# Sensorboard.net
KiCad netlist of a schematic drawn in EAGLE
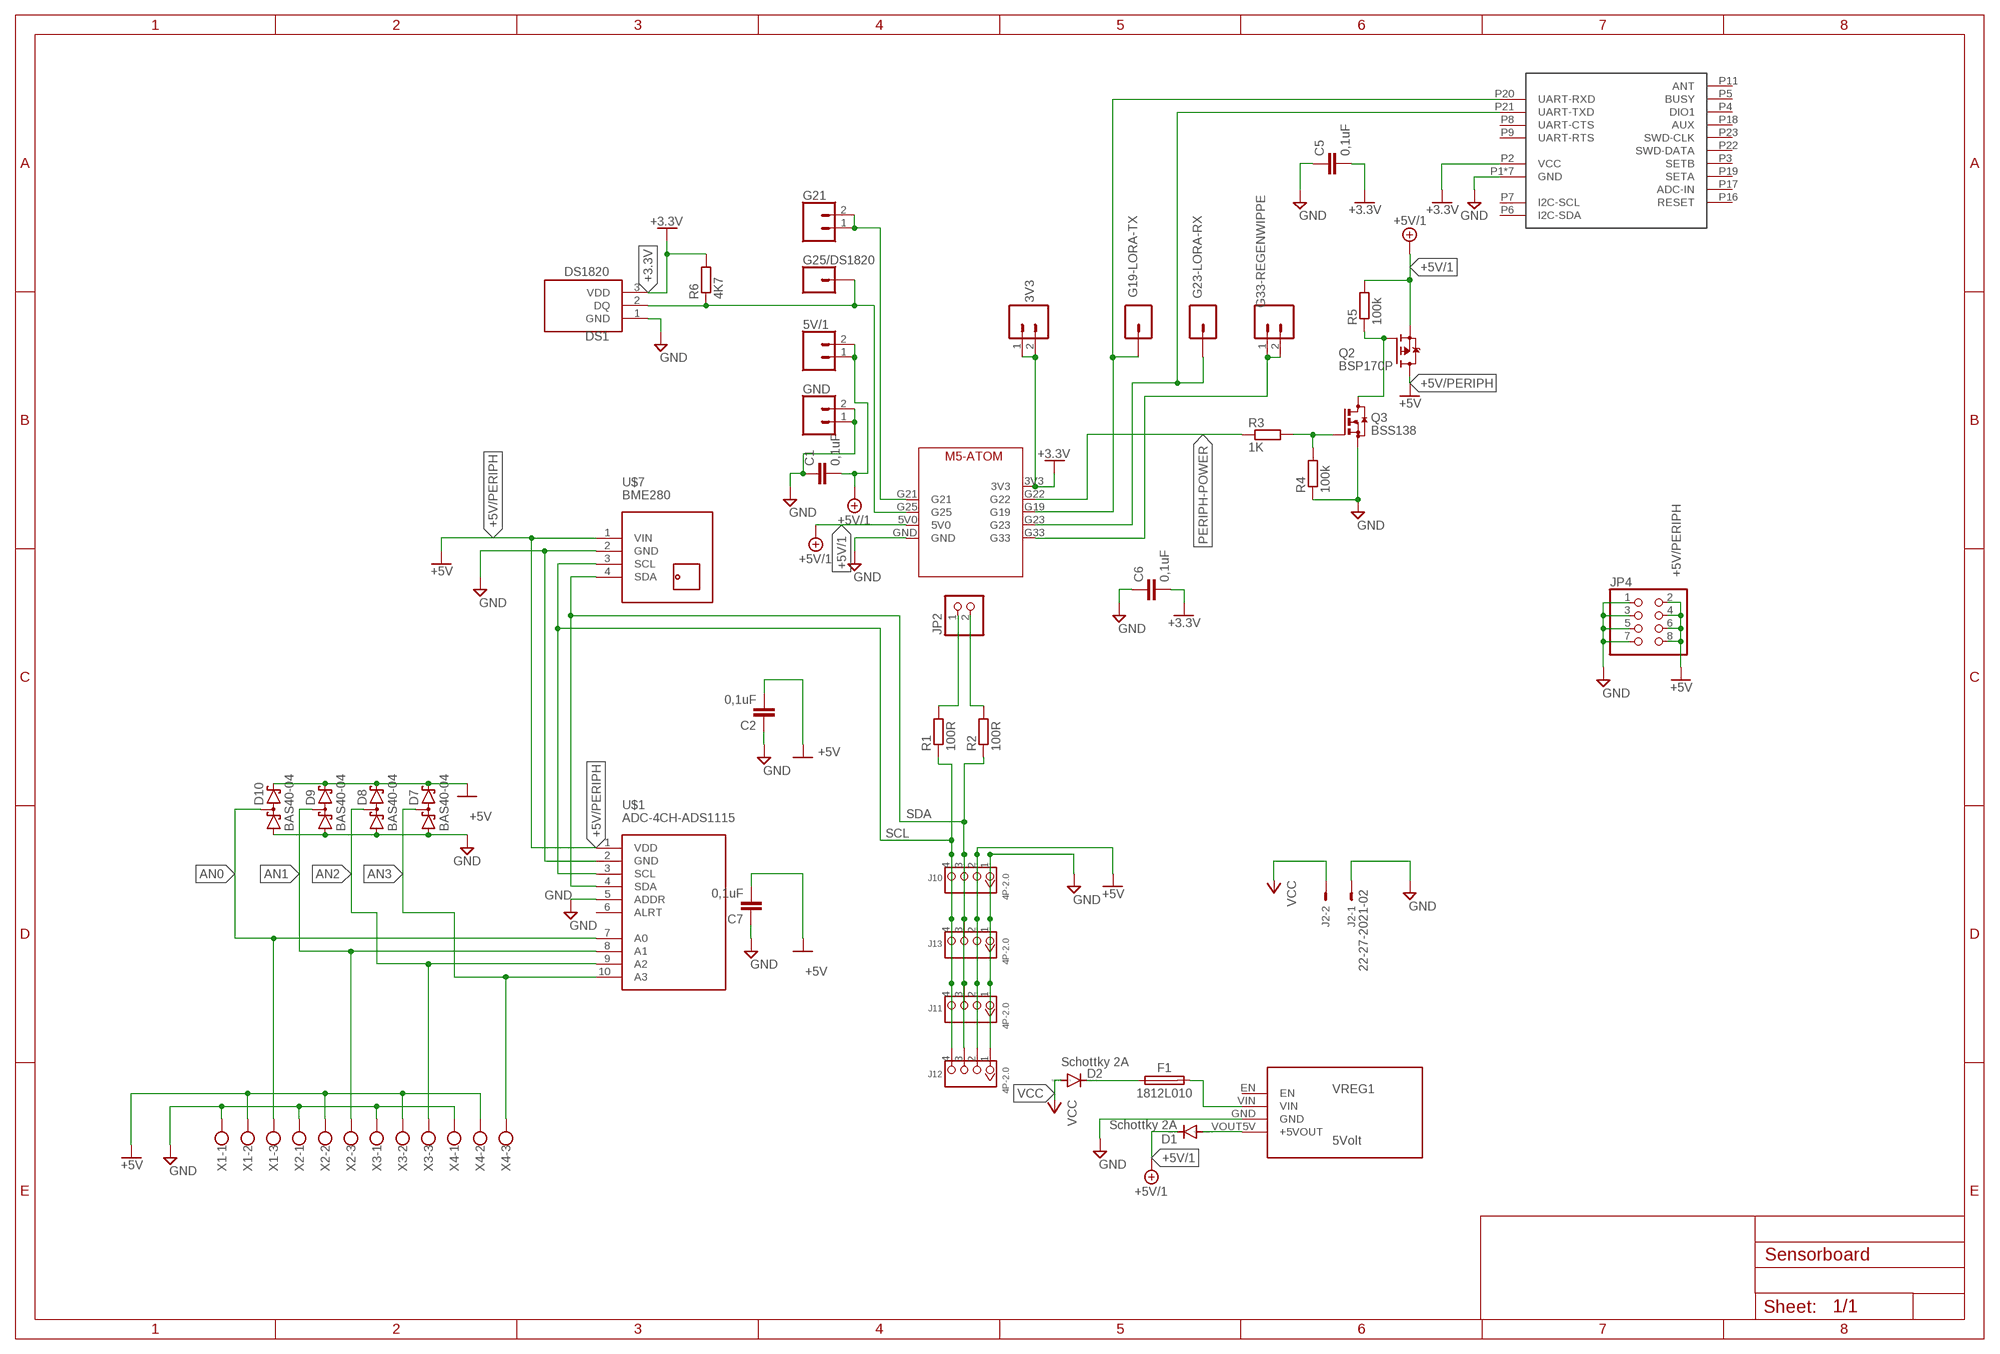
[diagram p0: schematic, sheet 1]

(export (version "E")
  (design (tool "Eeschema 10.0.6"))
  (components
    (comp (ref "3V3")
      (value "CONN_02")
      (footprint "eagle-import:1X02")
      (libsource (lib "eagle-import") (part "CONN_02"))
    )
    (comp (ref "5V/1")
      (value "CONN_02")
      (footprint "eagle-import:1X02")
      (libsource (lib "eagle-import") (part "CONN_02"))
    )
    (comp (ref "C1")
      (value "0,1uF")
      (footprint "eagle-import:C025-025X050")
      (libsource (lib "eagle-import") (part "C-EU025-025X050"))
    )
    (comp (ref "C2")
      (value "0,1uF")
      (footprint "eagle-import:C025-025X050")
      (libsource (lib "eagle-import") (part "C-EU025-025X050"))
    )
    (comp (ref "C5")
      (value "0,1uF")
      (footprint "eagle-import:C025-025X050")
      (libsource (lib "eagle-import") (part "C-EU025-025X050"))
    )
    (comp (ref "C6")
      (value "0,1uF")
      (footprint "eagle-import:C025-025X050")
      (libsource (lib "eagle-import") (part "C-EU025-025X050"))
    )
    (comp (ref "C7")
      (value "0,1uF")
      (footprint "eagle-import:C025-025X050")
      (libsource (lib "eagle-import") (part "C-EU025-025X050"))
    )
    (comp (ref "D1")
      (value "Schottky 2A")
      (footprint "eagle-import:DO41-10")
      (libsource (lib "eagle-import") (part "1N4004"))
    )
    (comp (ref "D2")
      (value "Schottky 2A")
      (footprint "eagle-import:DO41-10")
      (libsource (lib "eagle-import") (part "1N4004"))
    )
    (comp (ref "D7")
      (value "BAS40-04")
      (footprint "eagle-import:SOT23")
      (libsource (lib "eagle-import") (part "BAS40-04"))
    )
    (comp (ref "D8")
      (value "BAS40-04")
      (footprint "eagle-import:SOT23")
      (libsource (lib "eagle-import") (part "BAS40-04"))
    )
    (comp (ref "D9")
      (value "BAS40-04")
      (footprint "eagle-import:SOT23")
      (libsource (lib "eagle-import") (part "BAS40-04"))
    )
    (comp (ref "D10")
      (value "BAS40-04")
      (footprint "eagle-import:SOT23")
      (libsource (lib "eagle-import") (part "BAS40-04"))
    )
    (comp (ref "DS1")
      (value "DS1820")
      (footprint "eagle-import:DS1820-TO92")
      (libsource (lib "eagle-import") (part "DS1820"))
    )
    (comp (ref "F1")
      (value "1812L010")
      (footprint "eagle-import:FUSC4532X125")
      (fields (field (name "MANUFACTURER") "Littlefuse"))
      (libsource (lib "eagle-import") (part "1812L010"))
    )
    (comp (ref "G19-LORA-TX")
      (value "CONN_01")
      (footprint "eagle-import:1X01")
      (libsource (lib "eagle-import") (part "CONN_01"))
    )
    (comp (ref "G21")
      (value "CONN_02")
      (footprint "eagle-import:1X02")
      (libsource (lib "eagle-import") (part "CONN_02"))
    )
    (comp (ref "G23-LORA-RX")
      (value "CONN_01")
      (footprint "eagle-import:1X01")
      (libsource (lib "eagle-import") (part "CONN_01"))
    )
    (comp (ref "G25/DS1820")
      (value "CONN_01")
      (footprint "eagle-import:1X01")
      (libsource (lib "eagle-import") (part "CONN_01"))
    )
    (comp (ref "G33-REGENWIPPE")
      (value "CONN_02")
      (footprint "eagle-import:1X02")
      (libsource (lib "eagle-import") (part "CONN_02"))
    )
    (comp (ref "GND")
      (value "CONN_02")
      (footprint "eagle-import:1X02")
      (libsource (lib "eagle-import") (part "CONN_02"))
    )
    (comp (ref "J2")
      (value "22-27-2021-02")
      (footprint "eagle-import:6410-02")
      (fields (field (name "MF") "MOLEX"))
      (libsource (lib "eagle-import") (part "22-?-0227-2021"))
    )
    (comp (ref "J10")
      (value "4P-2.0")
      (footprint "eagle-import:HW4-2.0")
      (libsource (lib "eagle-import") (part "GROVE-CONNECTOR-DIP(4P-2.0)"))
    )
    (comp (ref "J11")
      (value "4P-2.0")
      (footprint "eagle-import:HW4-2.0")
      (libsource (lib "eagle-import") (part "GROVE-CONNECTOR-DIP(4P-2.0)"))
    )
    (comp (ref "J12")
      (value "4P-2.0")
      (footprint "eagle-import:HW4-2.0")
      (libsource (lib "eagle-import") (part "GROVE-CONNECTOR-DIP(4P-2.0)"))
    )
    (comp (ref "J13")
      (value "4P-2.0")
      (footprint "eagle-import:HW4-2.0")
      (libsource (lib "eagle-import") (part "GROVE-CONNECTOR-DIP(4P-2.0)"))
    )
    (comp (ref "JP2")
      (value "PINHD-1X2")
      (footprint "eagle-import:1X02")
      (libsource (lib "eagle-import") (part "PINHD-1X2"))
    )
    (comp (ref "JP4")
      (value "PINHD-2X4")
      (footprint "eagle-import:2X04")
      (libsource (lib "eagle-import") (part "PINHD-2X4"))
    )
    (comp (ref "M5-ATOM")
      (value "M5-ATOM")
      (footprint "eagle-import:M5-ATOM")
      (libsource (lib "eagle-import") (part "M5-ATOM"))
    )
    (comp (ref "Q2")
      (value "BSP170P")
      (footprint "eagle-import:SOT223")
      (libsource (lib "eagle-import") (part "BSP170P"))
    )
    (comp (ref "Q3")
      (value "BSS138")
      (footprint "eagle-import:SOT23")
      (libsource (lib "eagle-import") (part "BSS123"))
    )
    (comp (ref "R1")
      (value "100R")
      (footprint "eagle-import:0204_7")
      (libsource (lib "eagle-import") (part "R-EU_0204/7"))
    )
    (comp (ref "R2")
      (value "100R")
      (footprint "eagle-import:0204_7")
      (libsource (lib "eagle-import") (part "R-EU_0204/7"))
    )
    (comp (ref "R3")
      (value "1K")
      (footprint "eagle-import:R1206")
      (libsource (lib "eagle-import") (part "R-EU_R1206"))
    )
    (comp (ref "R4")
      (value "100k")
      (footprint "eagle-import:R1206")
      (libsource (lib "eagle-import") (part "R-EU_R1206"))
    )
    (comp (ref "R5")
      (value "100k")
      (footprint "eagle-import:R1206")
      (libsource (lib "eagle-import") (part "R-EU_R1206"))
    )
    (comp (ref "R6")
      (value "4K7")
      (footprint "eagle-import:R1206")
      (libsource (lib "eagle-import") (part "R-EU_R1206"))
    )
    (comp (ref "U$1")
      (value "ADC-4CH-ADS1115")
      (footprint "eagle-import:ADC-4CH-ADS1115")
      (libsource (lib "eagle-import") (part "ADC-4CH-ADS1115"))
    )
    (comp (ref "U$2")
      (value "E78-868LN22S")
      (footprint "eagle-import:E78-868LN22S")
      (libsource (lib "eagle-import") (part "E78-868LN22S"))
    )
    (comp (ref "U$7")
      (value "BME280")
      (footprint "eagle-import:TEMP-HUM-PRES-BME280")
      (libsource (lib "eagle-import") (part "TEMP-HUM-PRES-BME280"))
    )
    (comp (ref "VREG1")
      (value "5Volt")
      (footprint "eagle-import:VREG-STEPDOWN")
      (libsource (lib "eagle-import") (part "VREG-STEPDOWN"))
    )
    (comp (ref "X1")
      (value "W237-103-RB")
      (footprint "eagle-import:W237-103-RB")
      (libsource (lib "eagle-import") (part "W237-103-RB"))
    )
    (comp (ref "X2")
      (value "W237-103-RB")
      (footprint "eagle-import:W237-103-RB")
      (libsource (lib "eagle-import") (part "W237-103-RB"))
    )
    (comp (ref "X3")
      (value "W237-103-RB")
      (footprint "eagle-import:W237-103-RB")
      (libsource (lib "eagle-import") (part "W237-103-RB"))
    )
    (comp (ref "X4")
      (value "W237-103-RB")
      (footprint "eagle-import:W237-103-RB")
      (libsource (lib "eagle-import") (part "W237-103-RB"))
    )
  )
  (nets
    (net (code "1") (name "+3.3V") (class "Default")
      (node (ref "3V3") (pin "1") (pinfunction "1_1") (pintype "passive"))
      (node (ref "3V3") (pin "2") (pinfunction "2_2") (pintype "passive"))
      (node (ref "C5") (pin "2") (pinfunction "2_2") (pintype "passive"))
      (node (ref "C6") (pin "2") (pinfunction "2_2") (pintype "passive"))
      (node (ref "DS1") (pin "3") (pinfunction "VDD_3") (pintype "bidirectional"))
      (node (ref "M5-ATOM") (pin "3V3") (pinfunction "3V3_3V3") (pintype "bidirectional"))
      (node (ref "R6") (pin "2") (pinfunction "2_2") (pintype "passive"))
      (node (ref "U$2") (pin "P2") (pinfunction "VCC_P2") (pintype "bidirectional"))
    )
    (net (code "2") (name "+5V{slash}1") (class "Default")
      (node (ref "5V/1") (pin "1") (pinfunction "1_1") (pintype "passive"))
      (node (ref "5V/1") (pin "2") (pinfunction "2_2") (pintype "passive"))
      (node (ref "C1") (pin "2") (pinfunction "2_2") (pintype "passive"))
      (node (ref "D1") (pin "C") (pinfunction "C_C") (pintype "passive"))
      (node (ref "M5-ATOM") (pin "5V0") (pinfunction "5V0_5V0") (pintype "bidirectional"))
      (node (ref "Q2") (pin "3") (pinfunction "S_3") (pintype "passive"))
      (node (ref "R5") (pin "2") (pinfunction "2_2") (pintype "passive"))
    )
    (net (code "3") (name "+5V{slash}PERIPH") (class "Default")
      (node (ref "C2") (pin "2") (pinfunction "2_2") (pintype "passive"))
      (node (ref "C7") (pin "2") (pinfunction "2_2") (pintype "passive"))
      (node (ref "D10") (pin "2") (pinfunction "C2_2") (pintype "passive"))
      (node (ref "D7") (pin "2") (pinfunction "C2_2") (pintype "passive"))
      (node (ref "D8") (pin "2") (pinfunction "C2_2") (pintype "passive"))
      (node (ref "D9") (pin "2") (pinfunction "C2_2") (pintype "passive"))
      (node (ref "J10") (pin "2") (pinfunction "2_2") (pintype "bidirectional"))
      (node (ref "J11") (pin "2") (pinfunction "2_2") (pintype "bidirectional"))
      (node (ref "J12") (pin "2") (pinfunction "2_2") (pintype "bidirectional"))
      (node (ref "J13") (pin "2") (pinfunction "2_2") (pintype "bidirectional"))
      (node (ref "JP4") (pin "2") (pinfunction "2_2") (pintype "passive"))
      (node (ref "JP4") (pin "4") (pinfunction "4_4") (pintype "passive"))
      (node (ref "JP4") (pin "6") (pinfunction "6_6") (pintype "passive"))
      (node (ref "JP4") (pin "8") (pinfunction "8_8") (pintype "passive"))
      (node (ref "Q2") (pin "2") (pinfunction "D_2") (pintype "passive"))
      (node (ref "Q2") (pin "4") (pinfunction "D_4") (pintype "passive"))
      (node (ref "U$1") (pin "1") (pinfunction "VDD_1") (pintype "power_in"))
      (node (ref "U$7") (pin "1") (pinfunction "VIN_1") (pintype "power_in"))
      (node (ref "X1") (pin "2") (pinfunction "KL_2") (pintype "passive"))
      (node (ref "X2") (pin "2") (pinfunction "KL_2") (pintype "passive"))
      (node (ref "X3") (pin "2") (pinfunction "KL_2") (pintype "passive"))
      (node (ref "X4") (pin "2") (pinfunction "KL_2") (pintype "passive"))
    )
    (net (code "4") (name "/SCL") (class "Default")
      (node (ref "J10") (pin "4") (pinfunction "4_4") (pintype "bidirectional"))
      (node (ref "J11") (pin "4") (pinfunction "4_4") (pintype "bidirectional"))
      (node (ref "J12") (pin "4") (pinfunction "4_4") (pintype "bidirectional"))
      (node (ref "J13") (pin "4") (pinfunction "4_4") (pintype "bidirectional"))
      (node (ref "R1") (pin "1") (pinfunction "1_1") (pintype "passive"))
      (node (ref "U$1") (pin "3") (pinfunction "SCL_3") (pintype "bidirectional"))
      (node (ref "U$7") (pin "3") (pinfunction "SCL_3") (pintype "bidirectional"))
    )
    (net (code "5") (name "/SDA") (class "Default")
      (node (ref "J10") (pin "3") (pinfunction "3_3") (pintype "bidirectional"))
      (node (ref "J11") (pin "3") (pinfunction "3_3") (pintype "bidirectional"))
      (node (ref "J12") (pin "3") (pinfunction "3_3") (pintype "bidirectional"))
      (node (ref "J13") (pin "3") (pinfunction "3_3") (pintype "bidirectional"))
      (node (ref "R2") (pin "1") (pinfunction "1_1") (pintype "passive"))
      (node (ref "U$1") (pin "4") (pinfunction "SDA_4") (pintype "bidirectional"))
      (node (ref "U$7") (pin "4") (pinfunction "SDA_4") (pintype "bidirectional"))
    )
    (net (code "6") (name "AN0") (class "Default")
      (node (ref "D10") (pin "3") (pinfunction "C1A2_3") (pintype "passive"))
      (node (ref "U$1") (pin "7") (pinfunction "A0_7") (pintype "input"))
      (node (ref "X1") (pin "3") (pinfunction "KL_3") (pintype "passive"))
    )
    (net (code "7") (name "AN1") (class "Default")
      (node (ref "D9") (pin "3") (pinfunction "C1A2_3") (pintype "passive"))
      (node (ref "U$1") (pin "8") (pinfunction "A1_8") (pintype "input"))
      (node (ref "X2") (pin "3") (pinfunction "KL_3") (pintype "passive"))
    )
    (net (code "8") (name "AN2") (class "Default")
      (node (ref "D8") (pin "3") (pinfunction "C1A2_3") (pintype "passive"))
      (node (ref "U$1") (pin "9") (pinfunction "A2_9") (pintype "input"))
      (node (ref "X3") (pin "3") (pinfunction "KL_3") (pintype "passive"))
    )
    (net (code "9") (name "AN3") (class "Default")
      (node (ref "D7") (pin "3") (pinfunction "C1A2_3") (pintype "passive"))
      (node (ref "U$1") (pin "10") (pinfunction "A3_10") (pintype "input"))
      (node (ref "X4") (pin "3") (pinfunction "KL_3") (pintype "passive"))
    )
    (net (code "10") (name "GND") (class "Default")
      (node (ref "C1") (pin "1") (pinfunction "1_1") (pintype "passive"))
      (node (ref "C2") (pin "1") (pinfunction "1_1") (pintype "passive"))
      (node (ref "C5") (pin "1") (pinfunction "1_1") (pintype "passive"))
      (node (ref "C6") (pin "1") (pinfunction "1_1") (pintype "passive"))
      (node (ref "C7") (pin "1") (pinfunction "1_1") (pintype "passive"))
      (node (ref "D10") (pin "1") (pinfunction "A1_1") (pintype "passive"))
      (node (ref "D7") (pin "1") (pinfunction "A1_1") (pintype "passive"))
      (node (ref "D8") (pin "1") (pinfunction "A1_1") (pintype "passive"))
      (node (ref "D9") (pin "1") (pinfunction "A1_1") (pintype "passive"))
      (node (ref "DS1") (pin "1") (pinfunction "GND_1") (pintype "bidirectional"))
      (node (ref "GND") (pin "1") (pinfunction "1_1") (pintype "passive"))
      (node (ref "GND") (pin "2") (pinfunction "2_2") (pintype "passive"))
      (node (ref "J10") (pin "1") (pinfunction "1_1") (pintype "bidirectional"))
      (node (ref "J11") (pin "1") (pinfunction "1_1") (pintype "bidirectional"))
      (node (ref "J12") (pin "1") (pinfunction "1_1") (pintype "bidirectional"))
      (node (ref "J13") (pin "1") (pinfunction "1_1") (pintype "bidirectional"))
      (node (ref "J2") (pin "1") (pinfunction "S_1") (pintype "passive"))
      (node (ref "JP4") (pin "1") (pinfunction "1_1") (pintype "passive"))
      (node (ref "JP4") (pin "3") (pinfunction "3_3") (pintype "passive"))
      (node (ref "JP4") (pin "5") (pinfunction "5_5") (pintype "passive"))
      (node (ref "JP4") (pin "7") (pinfunction "7_7") (pintype "passive"))
      (node (ref "M5-ATOM") (pin "GND") (pinfunction "GND_GND") (pintype "bidirectional"))
      (node (ref "Q3") (pin "2") (pinfunction "S_2") (pintype "passive"))
      (node (ref "R4") (pin "1") (pinfunction "1_1") (pintype "passive"))
      (node (ref "U$1") (pin "2") (pinfunction "GND_2") (pintype "power_in"))
      (node (ref "U$1") (pin "5") (pinfunction "ADDR_5") (pintype "bidirectional"))
      (node (ref "U$2") (pin "P1") (pinfunction "GND_P1") (pintype "bidirectional"))
      (node (ref "U$2") (pin "P10") (pinfunction "GND_P10") (pintype "bidirectional"))
      (node (ref "U$2") (pin "P12") (pinfunction "GND_P12") (pintype "bidirectional"))
      (node (ref "U$2") (pin "P13") (pinfunction "GND_P13") (pintype "bidirectional"))
      (node (ref "U$2") (pin "P14") (pinfunction "GND_P14") (pintype "bidirectional"))
      (node (ref "U$2") (pin "P15") (pinfunction "GND_P15") (pintype "bidirectional"))
      (node (ref "U$2") (pin "P24") (pinfunction "GND_P24") (pintype "bidirectional"))
      (node (ref "U$7") (pin "2") (pinfunction "GND_2") (pintype "power_in"))
      (node (ref "VREG1") (pin "GND") (pinfunction "GND_GND") (pintype "bidirectional"))
      (node (ref "X1") (pin "1") (pinfunction "KL_1") (pintype "passive"))
      (node (ref "X2") (pin "1") (pinfunction "KL_1") (pintype "passive"))
      (node (ref "X3") (pin "1") (pinfunction "KL_1") (pintype "passive"))
      (node (ref "X4") (pin "1") (pinfunction "KL_1") (pintype "passive"))
    )
    (net (code "11") (name "Net-(D2-PadC)") (class "Default")
      (node (ref "D2") (pin "C") (pinfunction "C_C") (pintype "passive"))
      (node (ref "F1") (pin "1") (pinfunction "1_1") (pintype "passive"))
    )
    (net (code "12") (name "Net-(DS1-DQ)") (class "Default")
      (node (ref "DS1") (pin "2") (pinfunction "DQ_2") (pintype "bidirectional"))
      (node (ref "G25/DS1820") (pin "1") (pinfunction "1_1") (pintype "passive"))
      (node (ref "M5-ATOM") (pin "G25") (pinfunction "G25_G25") (pintype "bidirectional"))
      (node (ref "R6") (pin "1") (pinfunction "1_1") (pintype "passive"))
    )
    (net (code "13") (name "Net-(F1-Pad2)") (class "Default")
      (node (ref "F1") (pin "2") (pinfunction "2_2") (pintype "passive"))
      (node (ref "VREG1") (pin "VIN") (pinfunction "VIN_VIN") (pintype "bidirectional"))
    )
    (net (code "14") (name "Net-(G21-Pad1)") (class "Default")
      (node (ref "G21") (pin "1") (pinfunction "1_1") (pintype "passive"))
      (node (ref "G21") (pin "2") (pinfunction "2_2") (pintype "passive"))
      (node (ref "M5-ATOM") (pin "G21") (pinfunction "G21_G21") (pintype "bidirectional"))
    )
    (net (code "15") (name "Net-(G33-REGENWIPPE-Pad1)") (class "Default")
      (node (ref "G33-REGENWIPPE") (pin "1") (pinfunction "1_1") (pintype "passive"))
      (node (ref "G33-REGENWIPPE") (pin "2") (pinfunction "2_2") (pintype "passive"))
      (node (ref "M5-ATOM") (pin "G33") (pinfunction "G33_G33") (pintype "bidirectional"))
    )
    (net (code "16") (name "Net-(JP2-Pad1)") (class "Default")
      (node (ref "JP2") (pin "1") (pinfunction "1_1") (pintype "passive"))
      (node (ref "R1") (pin "2") (pinfunction "2_2") (pintype "passive"))
    )
    (net (code "17") (name "Net-(JP2-Pad2)") (class "Default")
      (node (ref "JP2") (pin "2") (pinfunction "2_2") (pintype "passive"))
      (node (ref "R2") (pin "2") (pinfunction "2_2") (pintype "passive"))
    )
    (net (code "18") (name "Net-(Q2-G)") (class "Default")
      (node (ref "Q2") (pin "1") (pinfunction "G_1") (pintype "passive"))
      (node (ref "Q3") (pin "3") (pinfunction "D_3") (pintype "passive"))
      (node (ref "R5") (pin "1") (pinfunction "1_1") (pintype "passive"))
    )
    (net (code "19") (name "Net-(Q3-G)") (class "Default")
      (node (ref "Q3") (pin "1") (pinfunction "G_1") (pintype "passive"))
      (node (ref "R3") (pin "2") (pinfunction "2_2") (pintype "passive"))
      (node (ref "R4") (pin "2") (pinfunction "2_2") (pintype "passive"))
    )
    (net (code "20") (name "Net-(U$2-UART-RXD)") (class "Default")
      (node (ref "G19-LORA-TX") (pin "1") (pinfunction "1_1") (pintype "passive"))
      (node (ref "M5-ATOM") (pin "G19") (pinfunction "G19_G19") (pintype "bidirectional"))
      (node (ref "U$2") (pin "P20") (pinfunction "UART-RXD_P20") (pintype "input"))
    )
    (net (code "21") (name "Net-(U$2-UART-TXD)") (class "Default")
      (node (ref "G23-LORA-RX") (pin "1") (pinfunction "1_1") (pintype "passive"))
      (node (ref "M5-ATOM") (pin "G23") (pinfunction "G23_G23") (pintype "bidirectional"))
      (node (ref "U$2") (pin "P21") (pinfunction "UART-TXD_P21") (pintype "output"))
    )
    (net (code "22") (name "Net-(VREG1-+5VOUT)") (class "Default")
      (node (ref "D1") (pin "A") (pinfunction "A_A") (pintype "passive"))
      (node (ref "VREG1") (pin "VOUT5V") (pinfunction "+5VOUT_VOUT5V") (pintype "bidirectional"))
    )
    (net (code "23") (name "PERIPH-POWER") (class "Default")
      (node (ref "M5-ATOM") (pin "G22") (pinfunction "G22_G22") (pintype "bidirectional"))
      (node (ref "R3") (pin "1") (pinfunction "1_1") (pintype "passive"))
    )
    (net (code "24") (name "VCC") (class "Default")
      (node (ref "D2") (pin "A") (pinfunction "A_A") (pintype "passive"))
      (node (ref "J2") (pin "2") (pinfunction "S_2") (pintype "passive"))
    )
    (net (code "25") (name "unconnected-(U$1-ALRT-Pad6)") (class "Default")
      (node (ref "U$1") (pin "6") (pinfunction "ALRT_6") (pintype "bidirectional"))
    )
    (net (code "26") (name "unconnected-(U$2-ADC-IN-PadP17)") (class "Default")
      (node (ref "U$2") (pin "P17") (pinfunction "ADC-IN_P17") (pintype "input"))
    )
    (net (code "27") (name "unconnected-(U$2-ANT-PadP11)") (class "Default")
      (node (ref "U$2") (pin "P11") (pinfunction "ANT_P11") (pintype "output"))
    )
    (net (code "28") (name "unconnected-(U$2-AUX-PadP18)") (class "Default")
      (node (ref "U$2") (pin "P18") (pinfunction "AUX_P18") (pintype "bidirectional"))
    )
    (net (code "29") (name "unconnected-(U$2-BUSY-PadP5)") (class "Default")
      (node (ref "U$2") (pin "P5") (pinfunction "BUSY_P5") (pintype "bidirectional"))
    )
    (net (code "30") (name "unconnected-(U$2-DIO1-PadP4)") (class "Default")
      (node (ref "U$2") (pin "P4") (pinfunction "DIO1_P4") (pintype "bidirectional"))
    )
    (net (code "31") (name "unconnected-(U$2-I2C-SCL-PadP7)") (class "Default")
      (node (ref "U$2") (pin "P7") (pinfunction "I2C-SCL_P7") (pintype "bidirectional"))
    )
    (net (code "32") (name "unconnected-(U$2-I2C-SDA-PadP6)") (class "Default")
      (node (ref "U$2") (pin "P6") (pinfunction "I2C-SDA_P6") (pintype "bidirectional"))
    )
    (net (code "33") (name "unconnected-(U$2-RESET-PadP16)") (class "Default")
      (node (ref "U$2") (pin "P16") (pinfunction "RESET_P16") (pintype "input"))
    )
    (net (code "34") (name "unconnected-(U$2-SETA-PadP19)") (class "Default")
      (node (ref "U$2") (pin "P19") (pinfunction "SETA_P19") (pintype "bidirectional"))
    )
    (net (code "35") (name "unconnected-(U$2-SETB-PadP3)") (class "Default")
      (node (ref "U$2") (pin "P3") (pinfunction "SETB_P3") (pintype "bidirectional"))
    )
    (net (code "36") (name "unconnected-(U$2-SWD-CLK-PadP23)") (class "Default")
      (node (ref "U$2") (pin "P23") (pinfunction "SWD-CLK_P23") (pintype "bidirectional"))
    )
    (net (code "37") (name "unconnected-(U$2-SWD-DATA-PadP22)") (class "Default")
      (node (ref "U$2") (pin "P22") (pinfunction "SWD-DATA_P22") (pintype "bidirectional"))
    )
    (net (code "38") (name "unconnected-(U$2-UART-CTS-PadP8)") (class "Default")
      (node (ref "U$2") (pin "P8") (pinfunction "UART-CTS_P8") (pintype "bidirectional"))
    )
    (net (code "39") (name "unconnected-(U$2-UART-RTS-PadP9)") (class "Default")
      (node (ref "U$2") (pin "P9") (pinfunction "UART-RTS_P9") (pintype "bidirectional"))
    )
    (net (code "40") (name "unconnected-(VREG1-PadEN)") (class "Default")
      (node (ref "VREG1") (pin "EN") (pinfunction "EN_EN") (pintype "bidirectional"))
    )
  )
)
